# PIC.net
KiCad netlist of a schematic drawn in Altium Designer
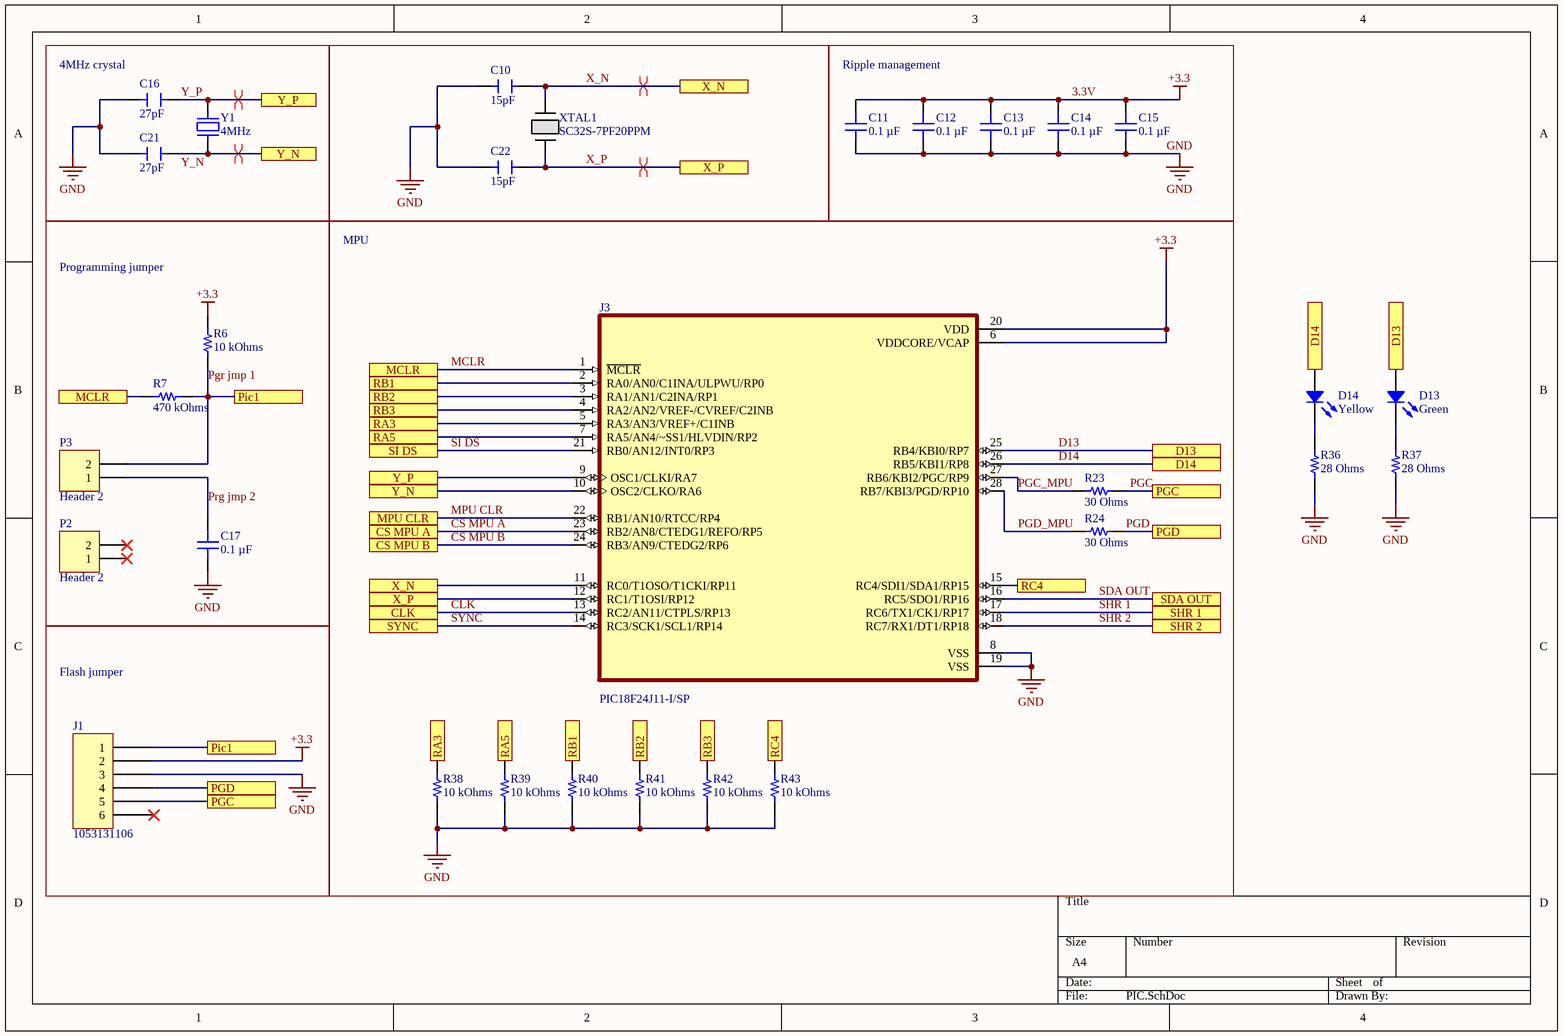
[diagram p0: PIC.SchDoc]

(export (version "E")
  (design (tool "Eeschema 10.0.6"))
  (components
    (comp (ref "C10")
      (value "15pF")
      (footprint "CAP MICA 27PF")
      (description "CAP MICA 15PF 5% 500V RADIAL")
      (libsource (lib "Signal Generator") (part "CAP MICA 10PF"))
    )
    (comp (ref "C11")
      (value "0.1 µF")
      (footprint "CAP 0805_2012")
      (description ".100UF 50.0V")
      (fields (field (name "PART NUMBER") "C0805X104K5RAC7210") (field (name "MANUFACTURER") "KEMET"))
      (libsource (lib "Celestial Altium Library - altium_library(1)") (part "Capacitor"))
    )
    (comp (ref "C12")
      (value "0.1 µF")
      (footprint "CAP 0805_2012")
      (description ".100UF 50.0V")
      (fields (field (name "PART NUMBER") "C0805X104K5RAC7210") (field (name "MANUFACTURER") "KEMET"))
      (libsource (lib "Celestial Altium Library - altium_library(1)") (part "Capacitor"))
    )
    (comp (ref "C13")
      (value "0.1 µF")
      (footprint "CAP 0805_2012")
      (description ".100UF 50.0V")
      (fields (field (name "PART NUMBER") "C0805X104K5RAC7210") (field (name "MANUFACTURER") "KEMET"))
      (libsource (lib "Celestial Altium Library - altium_library(1)") (part "Capacitor"))
    )
    (comp (ref "C14")
      (value "0.1 µF")
      (footprint "CAP 0805_2012")
      (description ".100UF 50.0V")
      (fields (field (name "PART NUMBER") "C0805X104K5RAC7210") (field (name "MANUFACTURER") "KEMET"))
      (libsource (lib "Celestial Altium Library - altium_library(1)") (part "Capacitor"))
    )
    (comp (ref "C15")
      (value "0.1 µF")
      (footprint "CAP 0805_2012")
      (description ".100UF 50.0V")
      (fields (field (name "PART NUMBER") "C0805X104K5RAC7210") (field (name "MANUFACTURER") "KEMET"))
      (libsource (lib "Celestial Altium Library - altium_library(1)") (part "Capacitor"))
    )
    (comp (ref "C16")
      (value "27pF")
      (footprint "CAP MICA 27PF")
      (description "CAP MICA 27PF 5% 500V RADIAL")
      (libsource (lib "Signal Generator") (part "CAP MICA 27PF"))
    )
    (comp (ref "C17")
      (value "0.1 µF")
      (footprint "CAP 0805_2012")
      (description ".100UF 50.0V")
      (fields (field (name "PART NUMBER") "C0805X104K5RAC7210") (field (name "MANUFACTURER") "KEMET"))
      (libsource (lib "Celestial Altium Library - altium_library(1)") (part "Capacitor"))
    )
    (comp (ref "C21")
      (value "27pF")
      (footprint "CAP MICA 27PF")
      (description "CAP MICA 27PF 5% 500V RADIAL")
      (libsource (lib "Signal Generator") (part "CAP MICA 27PF"))
    )
    (comp (ref "C22")
      (value "15pF")
      (footprint "CAP MICA 27PF")
      (description "CAP MICA 15PF 5% 500V RADIAL")
      (libsource (lib "Signal Generator") (part "CAP MICA 10PF"))
    )
    (comp (ref "D13")
      (value "Green")
      (footprint "LED 1206_3216 GREEN")
      (description "LED GREEN CLEAR 2SMD")
      (fields (field (name "PART NUMBER") "XZVG60W") (field (name "MANUFACTURER") "SunLED"))
      (libsource (lib "Celestial Altium Library - altium_library(1)") (part "LED"))
    )
    (comp (ref "D14")
      (value "Yellow")
      (footprint "LED 0805_2012 YELLOW")
      (description "LED YELLOW CLEAR CHIP SMD")
      (fields (field (name "PART NUMBER") "XZUY54W-1") (field (name "MANUFACTURER") "SunLED"))
      (libsource (lib "Celestial Altium Library - altium_library(1)") (part "LED"))
    )
    (comp (ref "J1")
      (value "1053131106")
      (footprint "MOLEX 1053131106")
      (description "CONN HEADER R/A 6POS 2.5MM")
      (fields (field (name "MANUFACTURER") "Molex"))
      (libsource (lib "Celestial Altium Library - altium_library(1)") (part "6 Pin"))
    )
    (comp (ref "J3")
      (value "PIC18F24J11-I/SP")
      (footprint "DIP787W45P254L3556H508Q28")
      (description "28-Pin, 16KB Flash, 4KB RAM, 12 MIPS, nanoWatt ¦ Microchip Technology Inc. PIC18F24J11-I/SP")
      (fields (field (name "MF") "Microchip"))
      (libsource (lib "PIC18F24J11-I_SP") (part "PIC18F24J11-I/SP"))
    )
    (comp (ref "P2")
      (value "Header 2")
      (footprint "HDR1X2")
      (description "Header, 2-Pin")
      (fields (field (name "PUBLISHER") "Altium Limited"))
      (libsource (lib "Miscellaneous Connectors") (part "Header 2"))
    )
    (comp (ref "P3")
      (value "Header 2")
      (footprint "HDR1X2")
      (description "Header, 2-Pin")
      (fields (field (name "PUBLISHER") "Altium Limited"))
      (libsource (lib "Miscellaneous Connectors") (part "Header 2"))
    )
    (comp (ref "R6")
      (value "10 kOhms")
      (footprint "RES 1210_3225")
      (description "CRMA1210 10K 1% EF E3")
      (fields (field (name "PART NUMBER") "CRMA1210AF10K0FKEF") (field (name "MANUFACTURER") "Vishay Dale"))
      (libsource (lib "Celestial Altium Library - altium_library(1)") (part "Resistor"))
    )
    (comp (ref "R7")
      (value "470 kOhms")
      (footprint "RES 1210_3225")
      (description "RES SMD 470K OHM 5% 1/2W 1210")
      (fields (field (name "PART NUMBER") "CRCW1210470KJNEA") (field (name "MANUFACTURER") "Vishay Dale"))
      (libsource (lib "Celestial Altium Library - altium_library(1)") (part "Resistor"))
    )
    (comp (ref "R23")
      (value "30 Ohms")
      (footprint "RES 1210_3225")
      (description "MP30R00 0.1% BULK")
      (fields
        (field (name "PART NUMBER") "MP30R00")
        (field (name "MANUFACTURER") "Vishay Foil Resistors (Division of Vishay Precision Group)")
      )
      (libsource (lib "Celestial Altium Library - altium_library(1)") (part "Resistor"))
    )
    (comp (ref "R24")
      (value "30 Ohms")
      (footprint "RES 1210_3225")
      (description "MP30R00 0.1% BULK")
      (fields
        (field (name "PART NUMBER") "MP30R00")
        (field (name "MANUFACTURER") "Vishay Foil Resistors (Division of Vishay Precision Group)")
      )
      (libsource (lib "Celestial Altium Library - altium_library(1)") (part "Resistor"))
    )
    (comp (ref "R36")
      (value "28 Ohms")
      (footprint "RES 2512_6432")
      (description "RES 28 OHM 1% 1W 2512")
      (fields
        (field (name "PART NUMBER") "RK73H3ATTE28R0F")
        (field (name "MANUFACTURER") "KOA Speer Electronics, Inc.")
      )
      (libsource (lib "Celestial Altium Library - altium_library(1)") (part "Resistor"))
    )
    (comp (ref "R37")
      (value "28 Ohms")
      (footprint "RES 2512_6432")
      (description "RES 28 OHM 1% 1W 2512")
      (fields
        (field (name "PART NUMBER") "RK73H3ATTE28R0F")
        (field (name "MANUFACTURER") "KOA Speer Electronics, Inc.")
      )
      (libsource (lib "Celestial Altium Library - altium_library(1)") (part "Resistor"))
    )
    (comp (ref "R38")
      (value "10 kOhms")
      (footprint "RES 1210_3225")
      (description "CRMA1210 10K 1% EF E3")
      (fields (field (name "PART NUMBER") "CRMA1210AF10K0FKEF") (field (name "MANUFACTURER") "Vishay Dale"))
      (libsource (lib "Celestial Altium Library - altium_library(1)") (part "Resistor"))
    )
    (comp (ref "R39")
      (value "10 kOhms")
      (footprint "RES 1210_3225")
      (description "CRMA1210 10K 1% EF E3")
      (fields (field (name "PART NUMBER") "CRMA1210AF10K0FKEF") (field (name "MANUFACTURER") "Vishay Dale"))
      (libsource (lib "Celestial Altium Library - altium_library(1)") (part "Resistor"))
    )
    (comp (ref "R40")
      (value "10 kOhms")
      (footprint "RES 1210_3225")
      (description "CRMA1210 10K 1% EF E3")
      (fields (field (name "PART NUMBER") "CRMA1210AF10K0FKEF") (field (name "MANUFACTURER") "Vishay Dale"))
      (libsource (lib "Celestial Altium Library - altium_library(1)") (part "Resistor"))
    )
    (comp (ref "R41")
      (value "10 kOhms")
      (footprint "RES 1210_3225")
      (description "CRMA1210 10K 1% EF E3")
      (fields (field (name "PART NUMBER") "CRMA1210AF10K0FKEF") (field (name "MANUFACTURER") "Vishay Dale"))
      (libsource (lib "Celestial Altium Library - altium_library(1)") (part "Resistor"))
    )
    (comp (ref "R42")
      (value "10 kOhms")
      (footprint "RES 1210_3225")
      (description "CRMA1210 10K 1% EF E3")
      (fields (field (name "PART NUMBER") "CRMA1210AF10K0FKEF") (field (name "MANUFACTURER") "Vishay Dale"))
      (libsource (lib "Celestial Altium Library - altium_library(1)") (part "Resistor"))
    )
    (comp (ref "R43")
      (value "10 kOhms")
      (footprint "RES 1210_3225")
      (description "CRMA1210 10K 1% EF E3")
      (fields (field (name "PART NUMBER") "CRMA1210AF10K0FKEF") (field (name "MANUFACTURER") "Vishay Dale"))
      (libsource (lib "Celestial Altium Library - altium_library(1)") (part "Resistor"))
    )
    (comp (ref "XTAL1")
      (value "SC32S-7PF20PPM")
      (footprint "XTAL_SC32S-7PF20PPM_EPS")
      (description "No Description Available")
      (libsource (lib "SC32S-7PF20PPM") (part "SC32S-7PF20PPM"))
    )
    (comp (ref "Y1")
      (value "4MHz")
      (footprint "ABRACON ABLS")
      (description "CRYSTAL 4.0000MHZ 20PF SMD")
      (fields
        (field (name "PART NUMBER") "ABLS-4.000MHZ-20-D-4-H-T")
        (field (name "MANUFACTURER") "Abracon LLC")
      )
      (libsource (lib "Celestial Altium Library - altium_library(1)") (part "Abracon Crystal ABLS"))
    )
  )
  (nets
    (net (code "1") (name "+3.3") (class "Default")
      (node (ref "C11") (pin "1") (pinfunction "1_1") (pintype "passive"))
      (node (ref "C12") (pin "2") (pinfunction "2_2") (pintype "passive"))
      (node (ref "C13") (pin "2") (pinfunction "2_2") (pintype "passive"))
      (node (ref "C14") (pin "2") (pinfunction "2_2") (pintype "passive"))
      (node (ref "C15") (pin "2") (pinfunction "2_2") (pintype "passive"))
      (node (ref "J1") (pin "2") (pinfunction "2_2") (pintype "passive"))
      (node (ref "J3") (pin "20") (pinfunction "VDD_20") (pintype "power_in"))
      (node (ref "J3") (pin "6") (pinfunction "VDDCORE/VCAP_6") (pintype "power_in"))
      (node (ref "R6") (pin "2") (pinfunction "2_2") (pintype "passive"))
    )
    (net (code "2") (name "/CLK") (class "Default")
      (node (ref "J3") (pin "13") (pinfunction "RC2/AN11/CTPLS/RP13_13") (pintype "bidirectional"))
    )
    (net (code "3") (name "/CS MPU A") (class "Default")
      (node (ref "J3") (pin "23") (pinfunction "RB2/AN8/CTEDG1/REFO/RP5_23") (pintype "bidirectional"))
    )
    (net (code "4") (name "/CS MPU B") (class "Default")
      (node (ref "J3") (pin "24") (pinfunction "RB3/AN9/CTEDG2/RP6_24") (pintype "bidirectional"))
    )
    (net (code "5") (name "/D13") (class "Default")
      (node (ref "D13") (pin "1") (pinfunction "1_1") (pintype "passive"))
      (node (ref "J3") (pin "25") (pinfunction "RB4/KBI0/RP7_25") (pintype "bidirectional"))
    )
    (net (code "6") (name "/D14") (class "Default")
      (node (ref "D14") (pin "1") (pinfunction "1_1") (pintype "passive"))
      (node (ref "J3") (pin "26") (pinfunction "RB5/KBI1/RP8_26") (pintype "bidirectional"))
    )
    (net (code "7") (name "/MCLR") (class "Default")
      (node (ref "J3") (pin "1") (pinfunction "~{MCLR}_1") (pintype "input"))
      (node (ref "R7") (pin "1") (pinfunction "1_1") (pintype "passive"))
    )
    (net (code "8") (name "/MPU CLR") (class "Default")
      (node (ref "J3") (pin "22") (pinfunction "RB1/AN10/RTCC/RP4_22") (pintype "bidirectional"))
    )
    (net (code "9") (name "/PGC") (class "Default")
      (node (ref "J1") (pin "5") (pinfunction "5_5") (pintype "passive"))
      (node (ref "R23") (pin "2") (pinfunction "2_2") (pintype "passive"))
    )
    (net (code "10") (name "/PGC_MPU") (class "Default")
      (node (ref "J3") (pin "27") (pinfunction "RB6/KBI2/PGC/RP9_27") (pintype "bidirectional"))
      (node (ref "R23") (pin "1") (pinfunction "1_1") (pintype "passive"))
    )
    (net (code "11") (name "/PGD") (class "Default")
      (node (ref "J1") (pin "4") (pinfunction "4_4") (pintype "passive"))
      (node (ref "R24") (pin "2") (pinfunction "2_2") (pintype "passive"))
    )
    (net (code "12") (name "/PGD_MPU") (class "Default")
      (node (ref "J3") (pin "28") (pinfunction "RB7/KBI3/PGD/RP10_28") (pintype "bidirectional"))
      (node (ref "R24") (pin "1") (pinfunction "1_1") (pintype "passive"))
    )
    (net (code "13") (name "/Pgr jmp 1") (class "Default")
      (node (ref "J1") (pin "1") (pinfunction "1_1") (pintype "passive"))
      (node (ref "P3") (pin "2") (pinfunction "2_2") (pintype "passive"))
      (node (ref "R6") (pin "1") (pinfunction "1_1") (pintype "passive"))
      (node (ref "R7") (pin "2") (pinfunction "2_2") (pintype "passive"))
    )
    (net (code "14") (name "/Prg jmp 2") (class "Default")
      (node (ref "C17") (pin "2") (pinfunction "2_2") (pintype "passive"))
      (node (ref "P3") (pin "1") (pinfunction "1_1") (pintype "passive"))
    )
    (net (code "15") (name "/RA3") (class "Default")
      (node (ref "J3") (pin "5") (pinfunction "RA3/AN3/VREF+/C1INB_5") (pintype "input"))
      (node (ref "R38") (pin "1") (pinfunction "1_1") (pintype "passive"))
    )
    (net (code "16") (name "/RA5") (class "Default")
      (node (ref "J3") (pin "7") (pinfunction "RA5/AN4/~SS1/HLVDIN/RP2_7") (pintype "input"))
      (node (ref "R39") (pin "2") (pinfunction "2_2") (pintype "passive"))
    )
    (net (code "17") (name "/RB1") (class "Default")
      (node (ref "J3") (pin "2") (pinfunction "RA0/AN0/C1INA/ULPWU/RP0_2") (pintype "input"))
      (node (ref "R40") (pin "2") (pinfunction "2_2") (pintype "passive"))
    )
    (net (code "18") (name "/RB2") (class "Default")
      (node (ref "J3") (pin "3") (pinfunction "RA1/AN1/C2INA/RP1_3") (pintype "input"))
      (node (ref "R41") (pin "2") (pinfunction "2_2") (pintype "passive"))
    )
    (net (code "19") (name "/RB3") (class "Default")
      (node (ref "J3") (pin "4") (pinfunction "RA2/AN2/VREF-/CVREF/C2INB_4") (pintype "input"))
      (node (ref "R42") (pin "2") (pinfunction "2_2") (pintype "passive"))
    )
    (net (code "20") (name "/RC4") (class "Default")
      (node (ref "J3") (pin "15") (pinfunction "RC4/SDI1/SDA1/RP15_15") (pintype "bidirectional"))
      (node (ref "R43") (pin "2") (pinfunction "2_2") (pintype "passive"))
    )
    (net (code "21") (name "/SDA OUT") (class "Default")
      (node (ref "J3") (pin "16") (pinfunction "RC5/SDO1/RP16_16") (pintype "bidirectional"))
    )
    (net (code "22") (name "/SHR 1") (class "Default")
      (node (ref "J3") (pin "17") (pinfunction "RC6/TX1/CK1/RP17_17") (pintype "bidirectional"))
    )
    (net (code "23") (name "/SHR 2") (class "Default")
      (node (ref "J3") (pin "18") (pinfunction "RC7/RX1/DT1/RP18_18") (pintype "bidirectional"))
    )
    (net (code "24") (name "/SI DS") (class "Default")
      (node (ref "J3") (pin "21") (pinfunction "RB0/AN12/INT0/RP3_21") (pintype "input"))
    )
    (net (code "25") (name "/SYNC") (class "Default")
      (node (ref "J3") (pin "14") (pinfunction "RC3/SCK1/SCL1/RP14_14") (pintype "bidirectional"))
    )
    (net (code "26") (name "/X_N") (class "Default")
      (node (ref "C10") (pin "2") (pinfunction "2_2") (pintype "passive"))
      (node (ref "J3") (pin "11") (pinfunction "RC0/T1OSO/T1CKI/RP11_11") (pintype "bidirectional"))
      (node (ref "XTAL1") (pin "2") (pinfunction "2_2") (pintype "passive"))
    )
    (net (code "27") (name "/X_P") (class "Default")
      (node (ref "C22") (pin "2") (pinfunction "2_2") (pintype "passive"))
      (node (ref "J3") (pin "12") (pinfunction "RC1/T1OSI/RP12_12") (pintype "bidirectional"))
      (node (ref "XTAL1") (pin "1") (pinfunction "1_1") (pintype "passive"))
    )
    (net (code "28") (name "/Y_N") (class "Default")
      (node (ref "C21") (pin "2") (pinfunction "2_2") (pintype "passive"))
      (node (ref "J3") (pin "10") (pinfunction "OSC2/CLKO/RA6_10") (pintype "bidirectional"))
      (node (ref "Y1") (pin "1") (pinfunction "1_1") (pintype "passive"))
    )
    (net (code "29") (name "/Y_P") (class "Default")
      (node (ref "C16") (pin "2") (pinfunction "2_2") (pintype "passive"))
      (node (ref "J3") (pin "9") (pinfunction "OSC1/CLKI/RA7_9") (pintype "bidirectional"))
      (node (ref "Y1") (pin "2") (pinfunction "2_2") (pintype "passive"))
    )
    (net (code "30") (name "GND") (class "Default")
      (node (ref "C10") (pin "1") (pinfunction "1_1") (pintype "passive"))
      (node (ref "C11") (pin "2") (pinfunction "2_2") (pintype "passive"))
      (node (ref "C12") (pin "1") (pinfunction "1_1") (pintype "passive"))
      (node (ref "C13") (pin "1") (pinfunction "1_1") (pintype "passive"))
      (node (ref "C14") (pin "1") (pinfunction "1_1") (pintype "passive"))
      (node (ref "C15") (pin "1") (pinfunction "1_1") (pintype "passive"))
      (node (ref "C16") (pin "1") (pinfunction "1_1") (pintype "passive"))
      (node (ref "C17") (pin "1") (pinfunction "1_1") (pintype "passive"))
      (node (ref "C21") (pin "1") (pinfunction "1_1") (pintype "passive"))
      (node (ref "C22") (pin "1") (pinfunction "1_1") (pintype "passive"))
      (node (ref "J1") (pin "3") (pinfunction "3_3") (pintype "passive"))
      (node (ref "J3") (pin "19") (pinfunction "VSS_19") (pintype "power_in"))
      (node (ref "J3") (pin "8") (pinfunction "VSS_8") (pintype "power_in"))
      (node (ref "R36") (pin "1") (pinfunction "1_1") (pintype "passive"))
      (node (ref "R37") (pin "1") (pinfunction "1_1") (pintype "passive"))
      (node (ref "R38") (pin "2") (pinfunction "2_2") (pintype "passive"))
      (node (ref "R39") (pin "1") (pinfunction "1_1") (pintype "passive"))
      (node (ref "R40") (pin "1") (pinfunction "1_1") (pintype "passive"))
      (node (ref "R41") (pin "1") (pinfunction "1_1") (pintype "passive"))
      (node (ref "R42") (pin "1") (pinfunction "1_1") (pintype "passive"))
      (node (ref "R43") (pin "1") (pinfunction "1_1") (pintype "passive"))
    )
    (net (code "31") (name "Net-(D13-Pad2)") (class "Default")
      (node (ref "D13") (pin "2") (pinfunction "2_2") (pintype "passive"))
      (node (ref "R37") (pin "2") (pinfunction "2_2") (pintype "passive"))
    )
    (net (code "32") (name "Net-(D14-Pad2)") (class "Default")
      (node (ref "D14") (pin "2") (pinfunction "2_2") (pintype "passive"))
      (node (ref "R36") (pin "2") (pinfunction "2_2") (pintype "passive"))
    )
    (net (code "33") (name "unconnected-(J1-Pad6)") (class "Default")
      (node (ref "J1") (pin "6") (pinfunction "6_6") (pintype "passive+no_connect"))
    )
    (net (code "34") (name "unconnected-(P2-Pad1)") (class "Default")
      (node (ref "P2") (pin "1") (pinfunction "1_1") (pintype "passive+no_connect"))
    )
    (net (code "35") (name "unconnected-(P2-Pad2)") (class "Default")
      (node (ref "P2") (pin "2") (pinfunction "2_2") (pintype "passive+no_connect"))
    )
  )
)
